# OpenMVX.net
KiCad netlist of a schematic drawn in Altium Designer
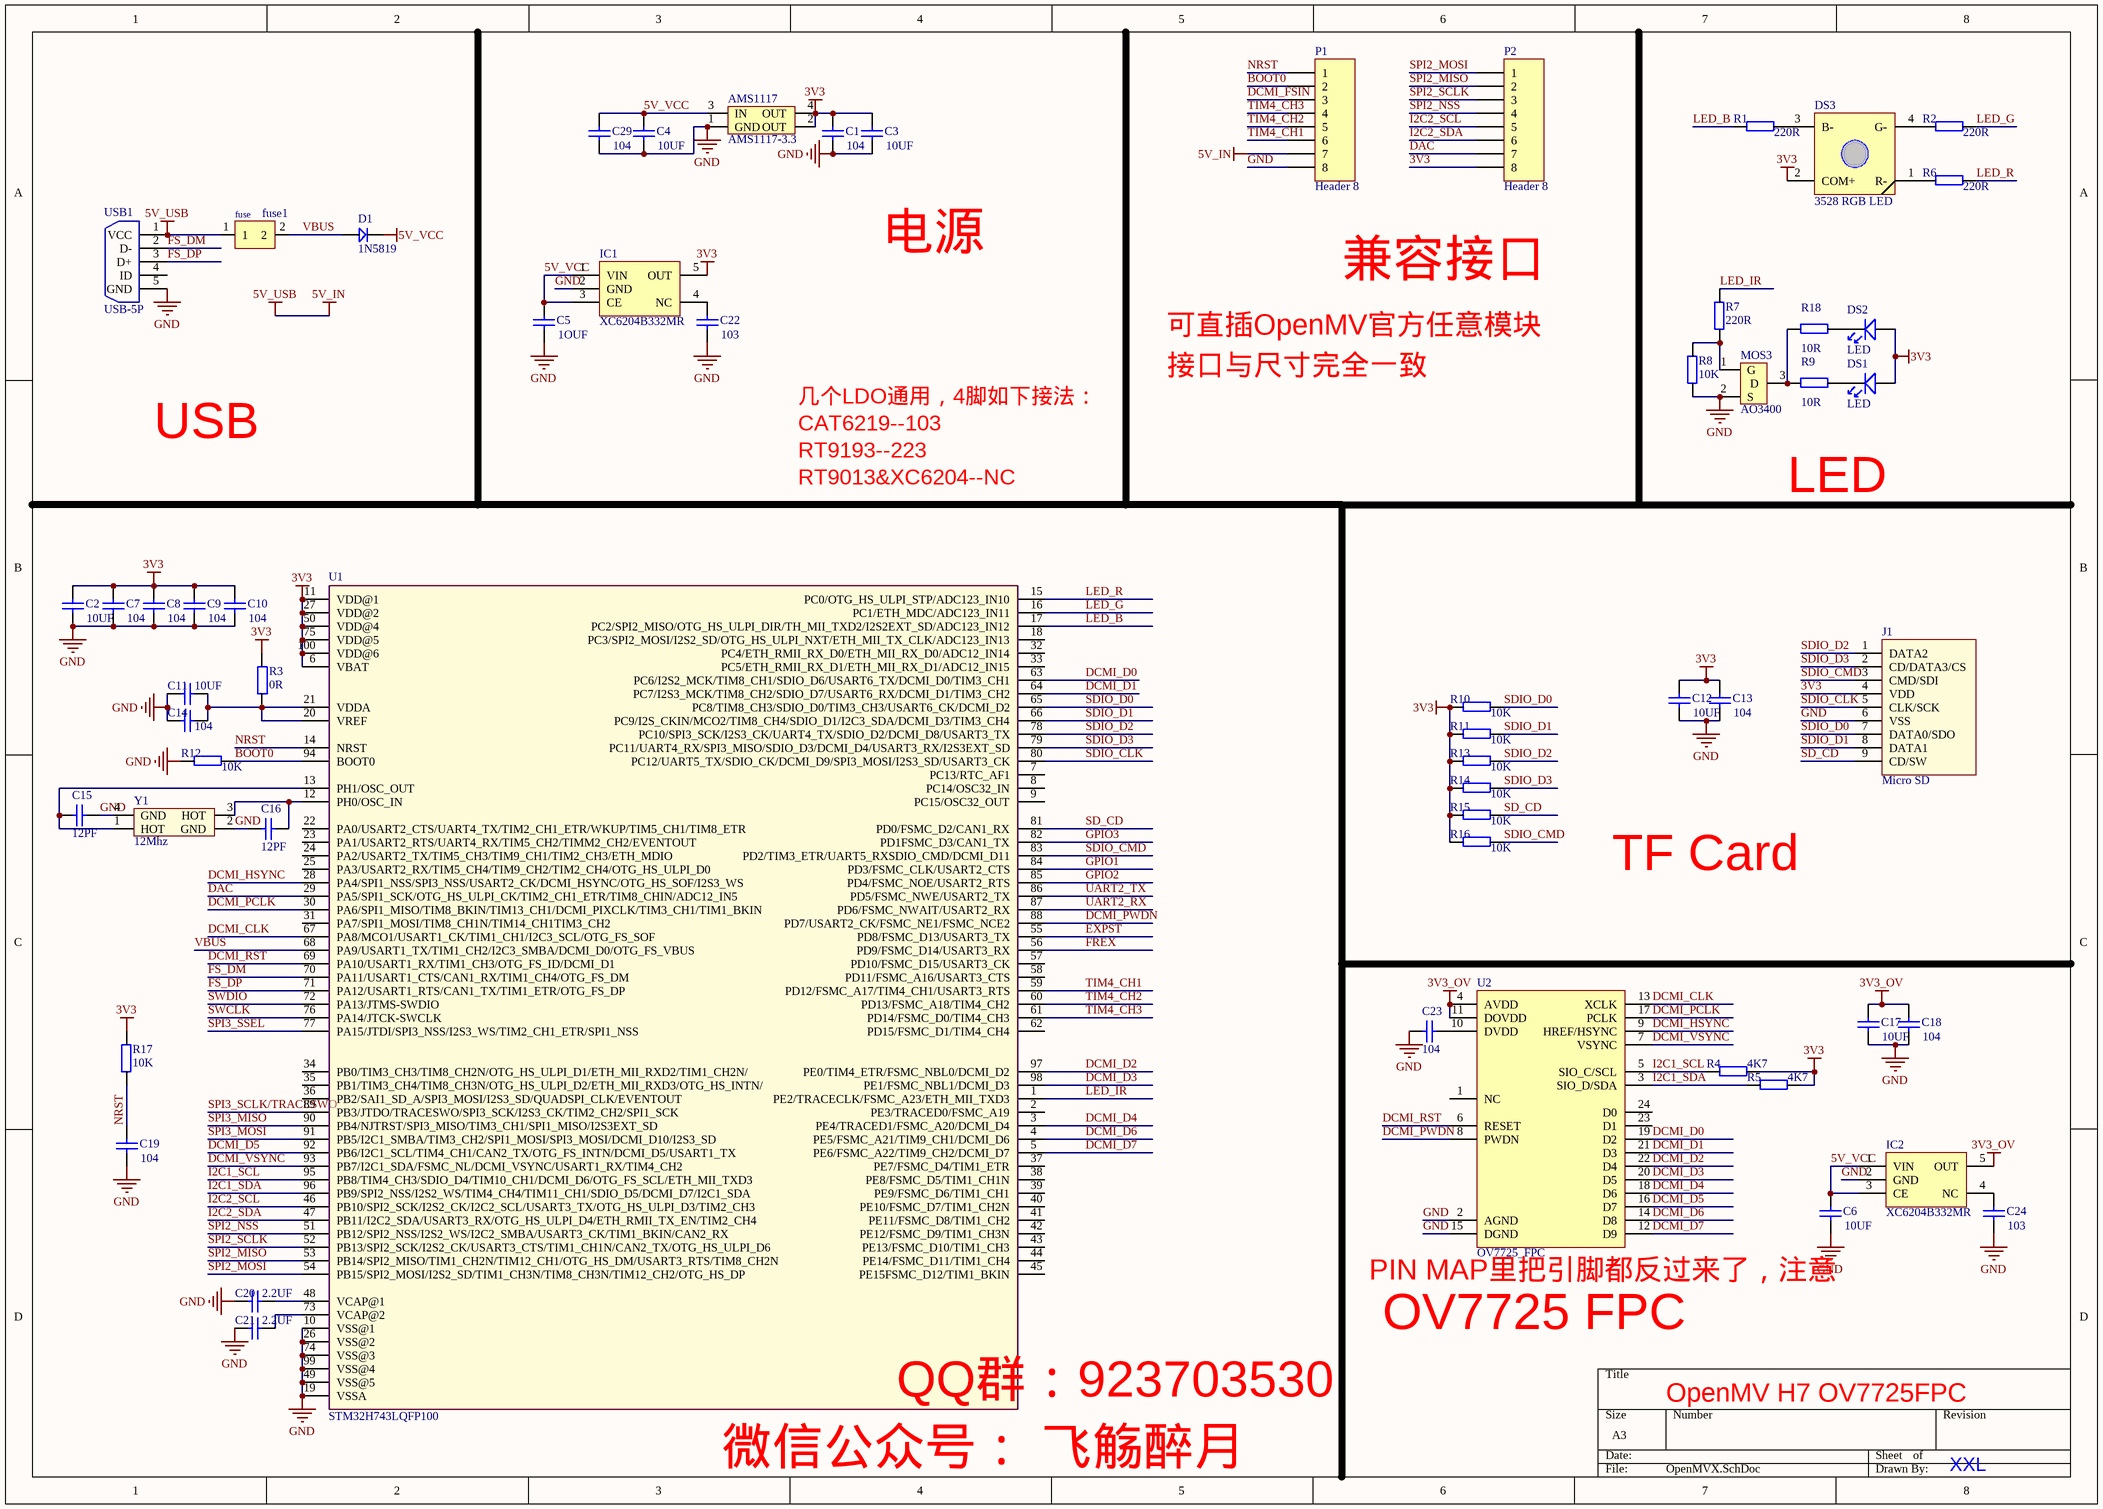
[diagram p0: OpenMVX.SchDoc]

(export (version "E")
  (design (tool "Eeschema 10.0.6"))
  (components
    (comp (ref "AMS1117")
      (value "AMS1117-3.3")
      (footprint "AMS1117")
      (libsource (lib "战舰STM32开发板底板封装库") (part "AMS1117"))
    )
    (comp (ref "C1") (value "104") (footprint "C_0603") (libsource (lib "myschlib") (part "C_0603")))
    (comp (ref "C2") (value "10UF") (footprint "C_0603") (libsource (lib "myschlib") (part "C_0603")))
    (comp (ref "C3") (value "10UF") (footprint "C_0603") (libsource (lib "myschlib") (part "C_0603")))
    (comp (ref "C4") (value "10UF") (footprint "C_0603") (libsource (lib "myschlib") (part "C_0603")))
    (comp (ref "C5") (value "1OUF") (footprint "C_0603") (libsource (lib "myschlib") (part "C_0603")))
    (comp (ref "C6") (value "10UF") (footprint "C_0603") (libsource (lib "myschlib") (part "C_0603")))
    (comp (ref "C7") (value "104") (footprint "C_0603") (libsource (lib "myschlib") (part "C_0603")))
    (comp (ref "C8") (value "104") (footprint "C_0603") (libsource (lib "myschlib") (part "C_0603")))
    (comp (ref "C9") (value "104") (footprint "C_0603") (libsource (lib "myschlib") (part "C_0603")))
    (comp (ref "C10") (value "104") (footprint "C_0603") (libsource (lib "myschlib") (part "C_0603")))
    (comp (ref "C11") (value "10UF") (footprint "C_0603") (libsource (lib "myschlib") (part "C_0603")))
    (comp (ref "C12") (value "10UF") (footprint "C_0603") (libsource (lib "myschlib") (part "C_0603")))
    (comp (ref "C13") (value "104") (footprint "C_0603") (libsource (lib "myschlib") (part "C_0603")))
    (comp (ref "C14") (value "104") (footprint "C_0603") (libsource (lib "myschlib") (part "C_0603")))
    (comp (ref "C15") (value "12PF") (footprint "C_0603") (libsource (lib "myschlib") (part "C_0603")))
    (comp (ref "C16") (value "12PF") (footprint "C_0603") (libsource (lib "myschlib") (part "C_0603")))
    (comp (ref "C17") (value "10UF") (footprint "C_0603") (libsource (lib "myschlib") (part "C_0603")))
    (comp (ref "C18") (value "104") (footprint "C_0603") (libsource (lib "myschlib") (part "C_0603")))
    (comp (ref "C19") (value "104") (footprint "C_0603") (libsource (lib "myschlib") (part "C_0603")))
    (comp (ref "C20") (value "2.2UF") (footprint "C_0603") (libsource (lib "myschlib") (part "C_0603")))
    (comp (ref "C21") (value "2.2UF") (footprint "C_0603") (libsource (lib "myschlib") (part "C_0603")))
    (comp (ref "C22") (value "103") (footprint "C_0603") (libsource (lib "myschlib") (part "C_0603")))
    (comp (ref "C23") (value "104") (footprint "C_0603") (libsource (lib "myschlib") (part "C_0603")))
    (comp (ref "C24") (value "103") (footprint "C_0603") (libsource (lib "myschlib") (part "C_0603")))
    (comp (ref "C29") (value "104") (footprint "C_0603") (libsource (lib "myschlib") (part "C_0603")))
    (comp (ref "D1")
      (value "1N5819")
      (footprint "mypcblib:SOD-323")
      (libsource (lib "战舰STM32开发板底板封装库") (part "D"))
    )
    (comp (ref "DS1") (value "LED") (footprint "mypcblib:LED-1206") (libsource (lib "myschlib") (part "LED")))
    (comp (ref "DS2") (value "LED") (footprint "mypcblib:LED-1206") (libsource (lib "myschlib") (part "LED")))
    (comp (ref "DS3")
      (value "3528 RGB LED")
      (footprint "3528/1210RGB LED")
      (libsource (lib "myschlib") (part "3528RGB LED"))
    )
    (comp (ref "fuse1") (value "fuse0603") (footprint "0603P") (libsource (lib "myschlib") (part "FUSE")))
    (comp (ref "IC1")
      (value "XC6204B332MR")
      (footprint "SOT23-5L")
      (description "LDO")
      (fields (field (name "版权归属") "源创客"))
      (libsource (lib "myschlib") (part "LDO XC6204"))
    )
    (comp (ref "IC2")
      (value "XC6204B332MR")
      (footprint "SOT23-5L")
      (description "LDO")
      (fields (field (name "版权归属") "源创客"))
      (libsource (lib "myschlib") (part "LDO XC6204"))
    )
    (comp (ref "J1")
      (value "Micro SD")
      (footprint "Micro SD")
      (description "Micro SD卡")
      (fields (field (name "版权归属") "源创客"))
      (libsource (lib "myschlib") (part "Micro SD"))
    )
    (comp (ref "MOS3")
      (value "AO3400")
      (footprint "SOT-23")
      (description "AO3400A")
      (libsource (lib "myschlib") (part "MOS-N"))
    )
    (comp (ref "P1")
      (value "Header 8")
      (footprint "1X08")
      (description "Header, 8-Pin")
      (fields (field (name "PUBLISHER") "Altium Limited"))
      (libsource (lib "myschlib") (part "Header 8"))
    )
    (comp (ref "P2")
      (value "Header 8")
      (footprint "1X08")
      (description "Header, 8-Pin")
      (fields (field (name "PUBLISHER") "Altium Limited"))
      (libsource (lib "myschlib") (part "Header 8"))
    )
    (comp (ref "R1") (value "220R") (footprint "0603P") (libsource (lib "myschlib") (part "R")))
    (comp (ref "R2") (value "220R") (footprint "0603P") (libsource (lib "myschlib") (part "R")))
    (comp (ref "R3") (value "0R") (footprint "0603P") (libsource (lib "myschlib") (part "R")))
    (comp (ref "R4") (value "4K7") (footprint "0603P") (libsource (lib "myschlib") (part "R")))
    (comp (ref "R5") (value "4K7") (footprint "0603P") (libsource (lib "myschlib") (part "R")))
    (comp (ref "R6") (value "220R") (footprint "0603P") (libsource (lib "myschlib") (part "R")))
    (comp (ref "R7") (value "220R") (footprint "0603P") (libsource (lib "myschlib") (part "R")))
    (comp (ref "R8") (value "10K") (footprint "0603P") (libsource (lib "myschlib") (part "R")))
    (comp (ref "R9") (value "10R") (footprint "0603P") (libsource (lib "myschlib") (part "R")))
    (comp (ref "R10") (value "10K") (footprint "0603P") (libsource (lib "myschlib") (part "R")))
    (comp (ref "R11") (value "10K") (footprint "0603P") (libsource (lib "myschlib") (part "R")))
    (comp (ref "R12") (value "10K") (footprint "0603P") (libsource (lib "myschlib") (part "R")))
    (comp (ref "R13") (value "10K") (footprint "0603P") (libsource (lib "myschlib") (part "R")))
    (comp (ref "R14") (value "10K") (footprint "0603P") (libsource (lib "myschlib") (part "R")))
    (comp (ref "R15") (value "10K") (footprint "0603P") (libsource (lib "myschlib") (part "R")))
    (comp (ref "R16") (value "10K") (footprint "0603P") (libsource (lib "myschlib") (part "R")))
    (comp (ref "R17") (value "10K") (footprint "0603P") (libsource (lib "myschlib") (part "R")))
    (comp (ref "R18") (value "10R") (footprint "0603P") (libsource (lib "myschlib") (part "R")))
    (comp (ref "U1")
      (value "STM32H743LQFP100")
      (footprint "LQFP-100PIN")
      (libsource (lib "myschlib") (part "STM32H743LQFP100"))
    )
    (comp (ref "U2")
      (value "OV7725_FPC")
      (footprint "FPC0.5 2H-WS-24P")
      (libsource (lib "myschlib") (part "OV7725 FPC 24P 0.5MM"))
    )
    (comp (ref "USB1")
      (value "USB-5P")
      (footprint "MICRO_USB")
      (description "微型USB母座")
      (fields (field (name "版权归属") "源创客"))
      (libsource (lib "myschlib") (part "USB-5P"))
    )
    (comp (ref "Y1")
      (value "12Mhz")
      (footprint "XTAL3225")
      (description "3225贴片无源晶振")
      (libsource (lib "STM32F767核心板封装库") (part "XTAL_3225"))
    )
  )
  (nets
    (net (code "1") (name "/BOOT0") (class "Default")
      (node (ref "P1") (pin "2") (pinfunction "2_2") (pintype "passive"))
      (node (ref "R12") (pin "1") (pintype "passive"))
      (node (ref "U1") (pin "94") (pinfunction "BOOT0_94") (pintype "passive"))
    )
    (net (code "2") (name "/DAC") (class "Default")
      (node (ref "P2") (pin "7") (pinfunction "7_7") (pintype "passive"))
      (node (ref "U1") (pin "29") (pinfunction "PA5/SPI1_SCK/OTG_HS_ULPI_CK/TIM2_CH1_ETR/TIM8_CHIN/ADC12_IN5_29") (pintype "passive"))
    )
    (net (code "3") (name "/DCMI_CLK") (class "Default")
      (node (ref "U1") (pin "67") (pinfunction "PA8/MCO1/USART1_CK/TIM1_CH1/I2C3_SCL/OTG_FS_SOF_67") (pintype "passive"))
      (node (ref "U2") (pin "13") (pinfunction "XCLK_13") (pintype "passive"))
    )
    (net (code "4") (name "/DCMI_D0") (class "Default")
      (node (ref "U1") (pin "63") (pinfunction "PC6/I2S2_MCK/TIM8_CH1/SDIO_D6/USART6_TX/DCMI_D0/TIM3_CH1_63") (pintype "passive"))
      (node (ref "U2") (pin "19") (pinfunction "D2_19") (pintype "passive"))
    )
    (net (code "5") (name "/DCMI_D1") (class "Default")
      (node (ref "U1") (pin "64") (pinfunction "PC7/I2S3_MCK/TIM8_CH2/SDIO_D7/USART6_RX/DCMI_D1/TIM3_CH2_64") (pintype "passive"))
      (node (ref "U2") (pin "21") (pinfunction "D3_21") (pintype "passive"))
    )
    (net (code "6") (name "/DCMI_D2") (class "Default")
      (node (ref "U1") (pin "97") (pinfunction "PE0/TIM4_ETR/FSMC_NBL0/DCMI_D2_97") (pintype "passive"))
      (node (ref "U2") (pin "22") (pinfunction "D4_22") (pintype "passive"))
    )
    (net (code "7") (name "/DCMI_D3") (class "Default")
      (node (ref "U1") (pin "98") (pinfunction "PE1/FSMC_NBL1/DCMI_D3_98") (pintype "passive"))
      (node (ref "U2") (pin "20") (pinfunction "D5_20") (pintype "passive"))
    )
    (net (code "8") (name "/DCMI_D4") (class "Default")
      (node (ref "U1") (pin "3") (pinfunction "PE4/TRACED1/FSMC_A20/DCMI_D4_3") (pintype "passive"))
      (node (ref "U2") (pin "18") (pinfunction "D6_18") (pintype "passive"))
    )
    (net (code "9") (name "/DCMI_D5") (class "Default")
      (node (ref "U1") (pin "92") (pinfunction "PB6/I2C1_SCL/TIM4_CH1/CAN2_TX/OTG_FS_INTN/DCMI_D5/USART1_TX_92") (pintype "passive"))
      (node (ref "U2") (pin "16") (pinfunction "D7_16") (pintype "passive"))
    )
    (net (code "10") (name "/DCMI_D6") (class "Default")
      (node (ref "U1") (pin "4") (pinfunction "PE5/FSMC_A21/TIM9_CH1/DCMI_D6_4") (pintype "passive"))
      (node (ref "U2") (pin "14") (pinfunction "D8_14") (pintype "passive"))
    )
    (net (code "11") (name "/DCMI_D7") (class "Default")
      (node (ref "U1") (pin "5") (pinfunction "PE6/FSMC_A22/TIM9_CH2/DCMI_D7_5") (pintype "passive"))
      (node (ref "U2") (pin "12") (pinfunction "D9_12") (pintype "passive"))
    )
    (net (code "12") (name "/DCMI_FSIN") (class "Default")
      (node (ref "P1") (pin "3") (pinfunction "3_3") (pintype "passive"))
    )
    (net (code "13") (name "/DCMI_HSYNC") (class "Default")
      (node (ref "U1") (pin "28") (pinfunction "PA4/SPI1_NSS/SPI3_NSS/USART2_CK/DCMI_HSYNC/OTG_HS_SOF/I2S3_WS_28") (pintype "passive"))
      (node (ref "U2") (pin "9") (pinfunction "HREF/HSYNC_9") (pintype "passive"))
    )
    (net (code "14") (name "/DCMI_PCLK") (class "Default")
      (node (ref "U1") (pin "30") (pinfunction "PA6/SPI1_MISO/TIM8_BKIN/TIM13_CH1/DCMI_PIXCLK/TIM3_CH1/TIM1_BKIN_30") (pintype "passive"))
      (node (ref "U2") (pin "17") (pinfunction "PCLK_17") (pintype "passive"))
    )
    (net (code "15") (name "/DCMI_PWDN") (class "Default")
      (node (ref "U1") (pin "88") (pinfunction "PD7/USART2_CK/FSMC_NE1/FSMC_NCE2_88") (pintype "passive"))
      (node (ref "U2") (pin "8") (pinfunction "PWDN_8") (pintype "passive"))
    )
    (net (code "16") (name "/DCMI_RST") (class "Default")
      (node (ref "U1") (pin "69") (pinfunction "PA10/USART1_RX/TIM1_CH3/OTG_FS_ID/DCMI_D1_69") (pintype "passive"))
      (node (ref "U2") (pin "6") (pinfunction "RESET_6") (pintype "passive"))
    )
    (net (code "17") (name "/DCMI_VSYNC") (class "Default")
      (node (ref "U1") (pin "93") (pinfunction "PB7/I2C1_SDA/FSMC_NL/DCMI_VSYNC/USART1_RX/TIM4_CH2_93") (pintype "passive"))
      (node (ref "U2") (pin "7") (pinfunction "VSYNC_7") (pintype "passive"))
    )
    (net (code "18") (name "/EXPST") (class "Default")
      (node (ref "U1") (pin "55") (pinfunction "PD8/FSMC_D13/USART3_TX_55") (pintype "passive"))
    )
    (net (code "19") (name "/FREX") (class "Default")
      (node (ref "U1") (pin "56") (pinfunction "PD9/FSMC_D14/USART3_RX_56") (pintype "passive"))
    )
    (net (code "20") (name "/FS_DM") (class "Default")
      (node (ref "U1") (pin "70") (pinfunction "PA11/USART1_CTS/CAN1_RX/TIM1_CH4/OTG_FS_DM_70") (pintype "passive"))
      (node (ref "USB1") (pin "2") (pinfunction "D-_2") (pintype "passive"))
    )
    (net (code "21") (name "/FS_DP") (class "Default")
      (node (ref "U1") (pin "71") (pinfunction "PA12/USART1_RTS/CAN1_TX/TIM1_ETR/OTG_FS_DP_71") (pintype "passive"))
      (node (ref "USB1") (pin "3") (pinfunction "D+_3") (pintype "passive"))
    )
    (net (code "22") (name "/GPIO1") (class "Default")
      (node (ref "U1") (pin "84") (pinfunction "PD3/FSMC_CLK/USART2_CTS_84") (pintype "passive"))
    )
    (net (code "23") (name "/GPIO2") (class "Default")
      (node (ref "U1") (pin "85") (pinfunction "PD4/FSMC_NOE/USART2_RTS_85") (pintype "passive"))
    )
    (net (code "24") (name "/GPIO3") (class "Default")
      (node (ref "U1") (pin "82") (pinfunction "PD1FSMC_D3/CAN1_TX_82") (pintype "passive"))
    )
    (net (code "25") (name "/I2C1_SCL") (class "Default")
      (node (ref "R4") (pin "2") (pintype "passive"))
      (node (ref "U1") (pin "95") (pinfunction "PB8/TIM4_CH3/SDIO_D4/TIM10_CH1/DCMI_D6/OTG_FS_SCL/ETH_MII_TXD3_95") (pintype "passive"))
      (node (ref "U2") (pin "5") (pinfunction "SIO_C/SCL_5") (pintype "passive"))
    )
    (net (code "26") (name "/I2C1_SDA") (class "Default")
      (node (ref "R5") (pin "2") (pintype "passive"))
      (node (ref "U1") (pin "96") (pinfunction "PB9/SPI2_NSS/I2S2_WS/TIM4_CH4/TIM11_CH1/SDIO_D5/DCMI_D7/I2C1_SDA_96") (pintype "passive"))
      (node (ref "U2") (pin "3") (pinfunction "SIO_D/SDA_3") (pintype "passive"))
    )
    (net (code "27") (name "/I2C2_SCL") (class "Default")
      (node (ref "P2") (pin "5") (pinfunction "5_5") (pintype "passive"))
      (node (ref "U1") (pin "46") (pinfunction "PB10/SPI2_SCK/I2S2_CK/I2C2_SCL/USART3_TX/OTG_HS_ULPI_D3/TIM2_CH3_46") (pintype "passive"))
    )
    (net (code "28") (name "/I2C2_SDA") (class "Default")
      (node (ref "P2") (pin "6") (pinfunction "6_6") (pintype "passive"))
      (node (ref "U1") (pin "47") (pinfunction "PB11/I2C2_SDA/USART3_RX/OTG_HS_ULPI_D4/ETH_RMII_TX_EN/TIM2_CH4_47") (pintype "passive"))
    )
    (net (code "29") (name "/LED_B") (class "Default")
      (node (ref "R1") (pin "2") (pintype "passive"))
      (node (ref "U1") (pin "17") (pinfunction "PC2/SPI2_MISO/OTG_HS_ULPI_DIR/TH_MII_TXD2/I2S2EXT_SD/ADC123_IN12_17") (pintype "passive"))
    )
    (net (code "30") (name "/LED_G") (class "Default")
      (node (ref "R2") (pin "1") (pintype "passive"))
      (node (ref "U1") (pin "16") (pinfunction "PC1/ETH_MDC/ADC123_IN11_16") (pintype "passive"))
    )
    (net (code "31") (name "/LED_IR") (class "Default")
      (node (ref "R7") (pin "1") (pintype "passive"))
      (node (ref "U1") (pin "1") (pinfunction "PE2/TRACECLK/FSMC_A23/ETH_MII_TXD3_1") (pintype "passive"))
    )
    (net (code "32") (name "/LED_R") (class "Default")
      (node (ref "R6") (pin "1") (pintype "passive"))
      (node (ref "U1") (pin "15") (pinfunction "PC0/OTG_HS_ULPI_STP/ADC123_IN10_15") (pintype "passive"))
    )
    (net (code "33") (name "/NRST") (class "Default")
      (node (ref "C19") (pin "2") (pinfunction "2_2") (pintype "passive"))
      (node (ref "P1") (pin "1") (pinfunction "1_1") (pintype "passive"))
      (node (ref "R17") (pin "2") (pintype "passive"))
      (node (ref "U1") (pin "14") (pinfunction "NRST_14") (pintype "passive"))
    )
    (net (code "34") (name "/SDIO_CLK") (class "Default")
      (node (ref "J1") (pin "5") (pinfunction "CLK/SCK_5") (pintype "passive"))
      (node (ref "U1") (pin "80") (pinfunction "PC12/UART5_TX/SDIO_CK/DCMI_D9/SPI3_MOSI/I2S3_SD/USART3_CK_80") (pintype "passive"))
    )
    (net (code "35") (name "/SDIO_CMD") (class "Default")
      (node (ref "J1") (pin "3") (pinfunction "CMD/SDI_3") (pintype "passive"))
      (node (ref "R16") (pin "1") (pintype "passive"))
      (node (ref "U1") (pin "83") (pinfunction "PD2/TIM3_ETR/UART5_RXSDIO_CMD/DCMI_D11_83") (pintype "passive"))
    )
    (net (code "36") (name "/SDIO_D0") (class "Default")
      (node (ref "J1") (pin "7") (pinfunction "DATA0/SDO_7") (pintype "passive"))
      (node (ref "R10") (pin "1") (pintype "passive"))
      (node (ref "U1") (pin "65") (pinfunction "PC8/TIM8_CH3/SDIO_D0/TIM3_CH3/USART6_CK/DCMI_D2_65") (pintype "passive"))
    )
    (net (code "37") (name "/SDIO_D1") (class "Default")
      (node (ref "J1") (pin "8") (pinfunction "DATA1_8") (pintype "passive"))
      (node (ref "R11") (pin "1") (pintype "passive"))
      (node (ref "U1") (pin "66") (pinfunction "PC9/I2S_CKIN/MCO2/TIM8_CH4/SDIO_D1/I2C3_SDA/DCMI_D3/TIM3_CH4_66") (pintype "passive"))
    )
    (net (code "38") (name "/SDIO_D2") (class "Default")
      (node (ref "J1") (pin "1") (pinfunction "DATA2_1") (pintype "passive"))
      (node (ref "R13") (pin "1") (pintype "passive"))
      (node (ref "U1") (pin "78") (pinfunction "PC10/SPI3_SCK/I2S3_CK/UART4_TX/SDIO_D2/DCMI_D8/USART3_TX_78") (pintype "passive"))
    )
    (net (code "39") (name "/SDIO_D3") (class "Default")
      (node (ref "J1") (pin "2") (pinfunction "CD/DATA3/CS_2") (pintype "passive"))
      (node (ref "R14") (pin "1") (pintype "passive"))
      (node (ref "U1") (pin "79") (pinfunction "PC11/UART4_RX/SPI3_MISO/SDIO_D3/DCMI_D4/USART3_RX/I2S3EXT_SD_79") (pintype "passive"))
    )
    (net (code "40") (name "/SD_CD") (class "Default")
      (node (ref "J1") (pin "9") (pinfunction "CD/SW_9") (pintype "passive"))
      (node (ref "R15") (pin "1") (pintype "passive"))
      (node (ref "U1") (pin "81") (pinfunction "PD0/FSMC_D2/CAN1_RX_81") (pintype "passive"))
    )
    (net (code "41") (name "/SPI2_MISO") (class "Default")
      (node (ref "P2") (pin "2") (pinfunction "2_2") (pintype "passive"))
      (node (ref "U1") (pin "53") (pinfunction "PB14/SPI2_MISO/TIM1_CH2N/TIM12_CH1/OTG_HS_DM/USART3_RTS/TIM8_CH2N_53") (pintype "passive"))
    )
    (net (code "42") (name "/SPI2_MOSI") (class "Default")
      (node (ref "P2") (pin "1") (pinfunction "1_1") (pintype "passive"))
      (node (ref "U1") (pin "54") (pinfunction "PB15/SPI2_MOSI/I2S2_SD/TIM1_CH3N/TIM8_CH3N/TIM12_CH2/OTG_HS_DP_54") (pintype "passive"))
    )
    (net (code "43") (name "/SPI2_NSS") (class "Default")
      (node (ref "P2") (pin "4") (pinfunction "4_4") (pintype "passive"))
      (node (ref "U1") (pin "51") (pinfunction "PB12/SPI2_NSS/I2S2_WS/I2C2_SMBA/USART3_CK/TIM1_BKIN/CAN2_RX_51") (pintype "passive"))
    )
    (net (code "44") (name "/SPI2_SCLK") (class "Default")
      (node (ref "P2") (pin "3") (pinfunction "3_3") (pintype "passive"))
      (node (ref "U1") (pin "52") (pinfunction "PB13/SPI2_SCK/I2S2_CK/USART3_CTS/TIM1_CH1N/CAN2_TX/OTG_HS_ULPI_D6_52") (pintype "passive"))
    )
    (net (code "45") (name "/SPI3_MISO") (class "Default")
      (node (ref "U1") (pin "90") (pinfunction "PB4/NJTRST/SPI3_MISO/TIM3_CH1/SPI1_MISO/I2S3EXT_SD_90") (pintype "passive"))
    )
    (net (code "46") (name "/SPI3_MOSI") (class "Default")
      (node (ref "U1") (pin "91") (pinfunction "PB5/I2C1_SMBA/TIM3_CH2/SPI1_MOSI/SPI3_MOSI/DCMI_D10/I2S3_SD_91") (pintype "passive"))
    )
    (net (code "47") (name "/SPI3_SCLK{slash}TRACESWO") (class "Default")
      (node (ref "U1") (pin "89") (pinfunction "PB3/JTDO/TRACESWO/SPI3_SCK/I2S3_CK/TIM2_CH2/SPI1_SCK_89") (pintype "passive"))
    )
    (net (code "48") (name "/SPI3_SSEL") (class "Default")
      (node (ref "U1") (pin "77") (pinfunction "PA15/JTDI/SPI3_NSS/I2S3_WS/TIM2_CH1_ETR/SPI1_NSS_77") (pintype "passive"))
    )
    (net (code "49") (name "/SWCLK") (class "Default")
      (node (ref "U1") (pin "76") (pinfunction "PA14/JTCK-SWCLK_76") (pintype "passive"))
    )
    (net (code "50") (name "/SWDIO") (class "Default")
      (node (ref "U1") (pin "72") (pinfunction "PA13/JTMS-SWDIO_72") (pintype "passive"))
    )
    (net (code "51") (name "/TIM4_CH1") (class "Default")
      (node (ref "P1") (pin "6") (pinfunction "6_6") (pintype "passive"))
      (node (ref "U1") (pin "59") (pinfunction "PD12/FSMC_A17/TIM4_CH1/USART3_RTS_59") (pintype "passive"))
    )
    (net (code "52") (name "/TIM4_CH2") (class "Default")
      (node (ref "P1") (pin "5") (pinfunction "5_5") (pintype "passive"))
      (node (ref "U1") (pin "60") (pinfunction "PD13/FSMC_A18/TIM4_CH2_60") (pintype "passive"))
    )
    (net (code "53") (name "/TIM4_CH3") (class "Default")
      (node (ref "P1") (pin "4") (pinfunction "4_4") (pintype "passive"))
      (node (ref "U1") (pin "61") (pinfunction "PD14/FSMC_D0/TIM4_CH3_61") (pintype "passive"))
    )
    (net (code "54") (name "/UART2_RX") (class "Default")
      (node (ref "U1") (pin "87") (pinfunction "PD6/FSMC_NWAIT/USART2_RX_87") (pintype "passive"))
    )
    (net (code "55") (name "/UART2_TX") (class "Default")
      (node (ref "U1") (pin "86") (pinfunction "PD5/FSMC_NWE/USART2_TX_86") (pintype "passive"))
    )
    (net (code "56") (name "/VBUS") (class "Default")
      (node (ref "D1") (pin "1") (pintype "passive"))
      (node (ref "U1") (pin "68") (pinfunction "PA9/USART1_TX/TIM1_CH2/I2C3_SMBA/DCMI_D0/OTG_FS_VBUS_68") (pintype "passive"))
      (node (ref "fuse1") (pin "2") (pinfunction "2_2") (pintype "passive"))
    )
    (net (code "57") (name "3V3") (class "Default")
      (node (ref "AMS1117") (pin "2") (pinfunction "OUT_2") (pintype "passive"))
      (node (ref "AMS1117") (pin "4") (pinfunction "OUT_4") (pintype "passive"))
      (node (ref "C1") (pin "2") (pinfunction "2_2") (pintype "passive"))
      (node (ref "C10") (pin "2") (pinfunction "2_2") (pintype "passive"))
      (node (ref "C12") (pin "2") (pinfunction "2_2") (pintype "passive"))
      (node (ref "C13") (pin "2") (pinfunction "2_2") (pintype "passive"))
      (node (ref "C2") (pin "2") (pinfunction "2_2") (pintype "passive"))
      (node (ref "C3") (pin "2") (pinfunction "2_2") (pintype "passive"))
      (node (ref "C7") (pin "2") (pinfunction "2_2") (pintype "passive"))
      (node (ref "C8") (pin "2") (pinfunction "2_2") (pintype "passive"))
      (node (ref "C9") (pin "2") (pinfunction "2_2") (pintype "passive"))
      (node (ref "DS1") (pin "1") (pinfunction "1_1") (pintype "passive"))
      (node (ref "DS2") (pin "1") (pinfunction "1_1") (pintype "passive"))
      (node (ref "DS3") (pin "2") (pinfunction "COM+_2") (pintype "passive"))
      (node (ref "IC1") (pin "5") (pinfunction "OUT_5") (pintype "passive"))
      (node (ref "J1") (pin "4") (pinfunction "VDD_4") (pintype "passive"))
      (node (ref "P2") (pin "8") (pinfunction "8_8") (pintype "passive"))
      (node (ref "R10") (pin "2") (pintype "passive"))
      (node (ref "R11") (pin "2") (pintype "passive"))
      (node (ref "R13") (pin "2") (pintype "passive"))
      (node (ref "R14") (pin "2") (pintype "passive"))
      (node (ref "R15") (pin "2") (pintype "passive"))
      (node (ref "R16") (pin "2") (pintype "passive"))
      (node (ref "R17") (pin "1") (pintype "passive"))
      (node (ref "R3") (pin "2") (pintype "passive"))
      (node (ref "R4") (pin "1") (pintype "passive"))
      (node (ref "R5") (pin "1") (pintype "passive"))
      (node (ref "U1") (pin "100") (pinfunction "VDD@6_100") (pintype "passive"))
      (node (ref "U1") (pin "11") (pinfunction "VDD@1_11") (pintype "passive"))
      (node (ref "U1") (pin "27") (pinfunction "VDD@2_27") (pintype "passive"))
      (node (ref "U1") (pin "50") (pinfunction "VDD@4_50") (pintype "passive"))
      (node (ref "U1") (pin "6") (pinfunction "VBAT_6") (pintype "passive"))
      (node (ref "U1") (pin "75") (pinfunction "VDD@5_75") (pintype "passive"))
    )
    (net (code "58") (name "3V3_OV") (class "Default")
      (node (ref "C17") (pin "2") (pinfunction "2_2") (pintype "passive"))
      (node (ref "C18") (pin "2") (pinfunction "2_2") (pintype "passive"))
      (node (ref "IC2") (pin "5") (pinfunction "OUT_5") (pintype "passive"))
      (node (ref "U2") (pin "11") (pinfunction "DOVDD_11") (pintype "passive"))
      (node (ref "U2") (pin "4") (pinfunction "AVDD_4") (pintype "passive"))
    )
    (net (code "59") (name "5V_IN") (class "Default")
      (node (ref "P1") (pin "7") (pinfunction "7_7") (pintype "passive"))
      (node (ref "USB1") (pin "1") (pinfunction "VCC_1") (pintype "passive"))
      (node (ref "fuse1") (pin "1") (pinfunction "1_1") (pintype "passive"))
    )
    (net (code "60") (name "5V_VCC") (class "Default")
      (node (ref "AMS1117") (pin "3") (pinfunction "IN_3") (pintype "passive"))
      (node (ref "C29") (pin "2") (pinfunction "2_2") (pintype "passive"))
      (node (ref "C4") (pin "2") (pinfunction "2_2") (pintype "passive"))
      (node (ref "C5") (pin "2") (pinfunction "2_2") (pintype "passive"))
      (node (ref "C6") (pin "2") (pinfunction "2_2") (pintype "passive"))
      (node (ref "D1") (pin "2") (pintype "passive"))
      (node (ref "IC1") (pin "1") (pinfunction "VIN_1") (pintype "passive"))
      (node (ref "IC1") (pin "3") (pinfunction "CE_3") (pintype "passive"))
      (node (ref "IC2") (pin "1") (pinfunction "VIN_1") (pintype "passive"))
      (node (ref "IC2") (pin "3") (pinfunction "CE_3") (pintype "passive"))
    )
    (net (code "61") (name "GND") (class "Default")
      (node (ref "AMS1117") (pin "1") (pinfunction "GND_1") (pintype "passive"))
      (node (ref "C1") (pin "1") (pinfunction "1_1") (pintype "passive"))
      (node (ref "C10") (pin "1") (pinfunction "1_1") (pintype "passive"))
      (node (ref "C11") (pin "2") (pinfunction "2_2") (pintype "passive"))
      (node (ref "C12") (pin "1") (pinfunction "1_1") (pintype "passive"))
      (node (ref "C13") (pin "1") (pinfunction "1_1") (pintype "passive"))
      (node (ref "C14") (pin "2") (pinfunction "2_2") (pintype "passive"))
      (node (ref "C15") (pin "1") (pinfunction "1_1") (pintype "passive"))
      (node (ref "C16") (pin "2") (pinfunction "2_2") (pintype "passive"))
      (node (ref "C17") (pin "1") (pinfunction "1_1") (pintype "passive"))
      (node (ref "C18") (pin "1") (pinfunction "1_1") (pintype "passive"))
      (node (ref "C19") (pin "1") (pinfunction "1_1") (pintype "passive"))
      (node (ref "C2") (pin "1") (pinfunction "1_1") (pintype "passive"))
      (node (ref "C20") (pin "2") (pinfunction "2_2") (pintype "passive"))
      (node (ref "C21") (pin "2") (pinfunction "2_2") (pintype "passive"))
      (node (ref "C22") (pin "1") (pinfunction "1_1") (pintype "passive"))
      (node (ref "C23") (pin "2") (pinfunction "2_2") (pintype "passive"))
      (node (ref "C24") (pin "1") (pinfunction "1_1") (pintype "passive"))
      (node (ref "C29") (pin "1") (pinfunction "1_1") (pintype "passive"))
      (node (ref "C3") (pin "1") (pinfunction "1_1") (pintype "passive"))
      (node (ref "C4") (pin "1") (pinfunction "1_1") (pintype "passive"))
      (node (ref "C5") (pin "1") (pinfunction "1_1") (pintype "passive"))
      (node (ref "C6") (pin "1") (pinfunction "1_1") (pintype "passive"))
      (node (ref "C7") (pin "1") (pinfunction "1_1") (pintype "passive"))
      (node (ref "C8") (pin "1") (pinfunction "1_1") (pintype "passive"))
      (node (ref "C9") (pin "1") (pinfunction "1_1") (pintype "passive"))
      (node (ref "IC1") (pin "2") (pinfunction "GND_2") (pintype "passive"))
      (node (ref "IC2") (pin "2") (pinfunction "GND_2") (pintype "passive"))
      (node (ref "J1") (pin "6") (pinfunction "VSS_6") (pintype "passive"))
      (node (ref "MOS3") (pin "2") (pinfunction "S_2") (pintype "passive"))
      (node (ref "P1") (pin "8") (pinfunction "8_8") (pintype "passive"))
      (node (ref "R12") (pin "2") (pintype "passive"))
      (node (ref "R8") (pin "2") (pintype "passive"))
      (node (ref "U1") (pin "10") (pinfunction "VSS@1_10") (pintype "passive"))
      (node (ref "U1") (pin "19") (pinfunction "VSSA_19") (pintype "passive"))
      (node (ref "U1") (pin "26") (pinfunction "VSS@2_26") (pintype "passive"))
      (node (ref "U1") (pin "49") (pinfunction "VSS@5_49") (pintype "passive"))
      (node (ref "U1") (pin "74") (pinfunction "VSS@3_74") (pintype "passive"))
      (node (ref "U1") (pin "99") (pinfunction "VSS@4_99") (pintype "passive"))
      (node (ref "U2") (pin "15") (pinfunction "DGND_15") (pintype "passive"))
      (node (ref "U2") (pin "2") (pinfunction "AGND_2") (pintype "passive"))
      (node (ref "USB1") (pin "5") (pinfunction "GND_5") (pintype "passive"))
      (node (ref "Y1") (pin "2") (pinfunction "GND_2") (pintype "passive"))
      (node (ref "Y1") (pin "4") (pinfunction "GND_4") (pintype "passive"))
    )
    (net (code "62") (name "Net-(DS1-Pad2)") (class "Default")
      (node (ref "DS1") (pin "2") (pinfunction "2_2") (pintype "passive"))
      (node (ref "R9") (pin "1") (pintype "passive"))
    )
    (net (code "63") (name "Net-(DS2-Pad2)") (class "Default")
      (node (ref "DS2") (pin "2") (pinfunction "2_2") (pintype "passive"))
      (node (ref "R18") (pin "1") (pintype "passive"))
    )
    (net (code "64") (name "Net-(DS3-B-)") (class "Default")
      (node (ref "DS3") (pin "3") (pinfunction "B-_3") (pintype "passive"))
      (node (ref "R1") (pin "1") (pintype "passive"))
    )
    (net (code "65") (name "Net-(DS3-G-)") (class "Default")
      (node (ref "DS3") (pin "4") (pinfunction "G-_4") (pintype "passive"))
      (node (ref "R2") (pin "2") (pintype "passive"))
    )
    (net (code "66") (name "Net-(DS3-R-)") (class "Default")
      (node (ref "DS3") (pin "1") (pinfunction "R-_1") (pintype "passive"))
      (node (ref "R6") (pin "2") (pintype "passive"))
    )
    (net (code "67") (name "Net-(IC1-NC)") (class "Default")
      (node (ref "C22") (pin "2") (pinfunction "2_2") (pintype "passive"))
      (node (ref "IC1") (pin "4") (pinfunction "NC_4") (pintype "passive"))
    )
    (net (code "68") (name "Net-(IC2-NC)") (class "Default")
      (node (ref "C24") (pin "2") (pinfunction "2_2") (pintype "passive"))
      (node (ref "IC2") (pin "4") (pinfunction "NC_4") (pintype "passive"))
    )
    (net (code "69") (name "Net-(MOS3-D)") (class "Default")
      (node (ref "MOS3") (pin "3") (pinfunction "D_3") (pintype "passive"))
      (node (ref "R18") (pin "2") (pintype "passive"))
      (node (ref "R9") (pin "2") (pintype "passive"))
    )
    (net (code "70") (name "Net-(MOS3-G)") (class "Default")
      (node (ref "MOS3") (pin "1") (pinfunction "G_1") (pintype "passive"))
      (node (ref "R7") (pin "2") (pintype "passive"))
      (node (ref "R8") (pin "1") (pintype "passive"))
    )
    (net (code "71") (name "Net-(U1-PH0{slash}OSC_IN)") (class "Default")
      (node (ref "C16") (pin "1") (pinfunction "1_1") (pintype "passive"))
      (node (ref "U1") (pin "12") (pinfunction "PH0/OSC_IN_12") (pintype "passive"))
      (node (ref "Y1") (pin "3") (pinfunction "HOT_3") (pintype "passive"))
    )
    (net (code "72") (name "Net-(U1-PH1{slash}OSC_OUT)") (class "Default")
      (node (ref "C15") (pin "2") (pinfunction "2_2") (pintype "passive"))
      (node (ref "U1") (pin "13") (pinfunction "PH1/OSC_OUT_13") (pintype "passive"))
      (node (ref "Y1") (pin "1") (pinfunction "HOT_1") (pintype "passive"))
    )
    (net (code "73") (name "Net-(U1-VCAP@1)") (class "Default")
      (node (ref "C20") (pin "1") (pinfunction "1_1") (pintype "passive"))
      (node (ref "U1") (pin "48") (pinfunction "VCAP@1_48") (pintype "passive"))
    )
    (net (code "74") (name "Net-(U1-VCAP@2)") (class "Default")
      (node (ref "C21") (pin "1") (pinfunction "1_1") (pintype "passive"))
      (node (ref "U1") (pin "73") (pinfunction "VCAP@2_73") (pintype "passive"))
    )
    (net (code "75") (name "Net-(U1-VDDA)") (class "Default")
      (node (ref "C11") (pin "1") (pinfunction "1_1") (pintype "passive"))
      (node (ref "C14") (pin "1") (pinfunction "1_1") (pintype "passive"))
      (node (ref "R3") (pin "1") (pintype "passive"))
      (node (ref "U1") (pin "20") (pinfunction "VREF_20") (pintype "passive"))
      (node (ref "U1") (pin "21") (pinfunction "VDDA_21") (pintype "passive"))
    )
    (net (code "76") (name "Net-(U2-DVDD)") (class "Default")
      (node (ref "C23") (pin "1") (pinfunction "1_1") (pintype "passive"))
      (node (ref "U2") (pin "10") (pinfunction "DVDD_10") (pintype "passive"))
    )
    (net (code "77") (name "unconnected-(U1-PA0{slash}USART2_CTS{slash}UART4_TX{slash}TIM2_CH1_ETR{slash}WKUP{slash}TIM5_CH1{slash}TIM8_ETR-Pad22)") (class "Default")
      (node (ref "U1") (pin "22") (pinfunction "PA0/USART2_CTS/UART4_TX/TIM2_CH1_ETR/WKUP/TIM5_CH1/TIM8_ETR_22") (pintype "passive"))
    )
    (net (code "78") (name "unconnected-(U1-PA1{slash}USART2_RTS{slash}UART4_RX{slash}TIM5_CH2{slash}TIMM2_CH2{slash}EVENTOUT-Pad23)") (class "Default")
      (node (ref "U1") (pin "23") (pinfunction "PA1/USART2_RTS/UART4_RX/TIM5_CH2/TIMM2_CH2/EVENTOUT_23") (pintype "passive"))
    )
    (net (code "79") (name "unconnected-(U1-PA2{slash}USART2_TX{slash}TIM5_CH3{slash}TIM9_CH1{slash}TIM2_CH3{slash}ETH_MDIO-Pad24)") (class "Default")
      (node (ref "U1") (pin "24") (pinfunction "PA2/USART2_TX/TIM5_CH3/TIM9_CH1/TIM2_CH3/ETH_MDIO_24") (pintype "passive"))
    )
    (net (code "80") (name "unconnected-(U1-PA3{slash}USART2_RX{slash}TIM5_CH4{slash}TIM9_CH2{slash}TIM2_CH4{slash}OTG_HS_ULPI_D0-Pad25)") (class "Default")
      (node (ref "U1") (pin "25") (pinfunction "PA3/USART2_RX/TIM5_CH4/TIM9_CH2/TIM2_CH4/OTG_HS_ULPI_D0_25") (pintype "passive"))
    )
    (net (code "81") (name "unconnected-(U1-PA7{slash}SPI1_MOSI{slash}TIM8_CH1N{slash}TIM14_CH1TIM3_CH2-Pad31)") (class "Default")
      (node (ref "U1") (pin "31") (pinfunction "PA7/SPI1_MOSI/TIM8_CH1N/TIM14_CH1TIM3_CH2_31") (pintype "passive"))
    )
    (net (code "82") (name "unconnected-(U1-PB0{slash}TIM3_CH3{slash}TIM8_CH2N{slash}OTG_HS_ULPI_D1{slash}ETH_MII_RXD2{slash}TIM1_CH2N{slash}-Pad34)") (class "Default")
      (node (ref "U1") (pin "34") (pinfunction "PB0/TIM3_CH3/TIM8_CH2N/OTG_HS_ULPI_D1/ETH_MII_RXD2/TIM1_CH2N/_34") (pintype "passive"))
    )
    (net (code "83") (name "unconnected-(U1-PB1{slash}TIM3_CH4{slash}TIM8_CH3N{slash}OTG_HS_ULPI_D2{slash}ETH_MII_RXD3{slash}OTG_HS_INTN{slash}-Pad35)") (class "Default")
      (node (ref "U1") (pin "35") (pinfunction "PB1/TIM3_CH4/TIM8_CH3N/OTG_HS_ULPI_D2/ETH_MII_RXD3/OTG_HS_INTN/_35") (pintype "passive"))
    )
    (net (code "84") (name "unconnected-(U1-PB2{slash}SAI1_SD_A{slash}SPI3_MOSI{slash}I2S3_SD{slash}QUADSPI_CLK{slash}EVENTOUT-Pad36)") (class "Default")
      (node (ref "U1") (pin "36") (pinfunction "PB2/SAI1_SD_A/SPI3_MOSI/I2S3_SD/QUADSPI_CLK/EVENTOUT_36") (pintype "passive"))
    )
    (net (code "85") (name "unconnected-(U1-PC3{slash}SPI2_MOSI{slash}I2S2_SD{slash}OTG_HS_ULPI_NXT{slash}ETH_MII_TX_CLK{slash}ADC123_IN13-Pad18)") (class "Default")
      (node (ref "U1") (pin "18") (pinfunction "PC3/SPI2_MOSI/I2S2_SD/OTG_HS_ULPI_NXT/ETH_MII_TX_CLK/ADC123_IN13_18") (pintype "passive"))
    )
    (net (code "86") (name "unconnected-(U1-PC4{slash}ETH_RMII_RX_D0{slash}ETH_MII_RX_D0{slash}ADC12_IN14-Pad32)") (class "Default")
      (node (ref "U1") (pin "32") (pinfunction "PC4/ETH_RMII_RX_D0/ETH_MII_RX_D0/ADC12_IN14_32") (pintype "passive"))
    )
    (net (code "87") (name "unconnected-(U1-PC5{slash}ETH_RMII_RX_D1{slash}ETH_MII_RX_D1{slash}ADC12_IN15-Pad33)") (class "Default")
      (node (ref "U1") (pin "33") (pinfunction "PC5/ETH_RMII_RX_D1/ETH_MII_RX_D1/ADC12_IN15_33") (pintype "passive"))
    )
    (net (code "88") (name "unconnected-(U1-PC13{slash}RTC_AF1-Pad7)") (class "Default")
      (node (ref "U1") (pin "7") (pinfunction "PC13/RTC_AF1_7") (pintype "passive"))
    )
    (net (code "89") (name "unconnected-(U1-PC14{slash}OSC32_IN-Pad8)") (class "Default")
      (node (ref "U1") (pin "8") (pinfunction "PC14/OSC32_IN_8") (pintype "passive"))
    )
    (net (code "90") (name "unconnected-(U1-PC15{slash}OSC32_OUT-Pad9)") (class "Default")
      (node (ref "U1") (pin "9") (pinfunction "PC15/OSC32_OUT_9") (pintype "passive"))
    )
    (net (code "91") (name "unconnected-(U1-PD10{slash}FSMC_D15{slash}USART3_CK-Pad57)") (class "Default")
      (node (ref "U1") (pin "57") (pinfunction "PD10/FSMC_D15/USART3_CK_57") (pintype "passive"))
    )
    (net (code "92") (name "unconnected-(U1-PD11{slash}FSMC_A16{slash}USART3_CTS-Pad58)") (class "Default")
      (node (ref "U1") (pin "58") (pinfunction "PD11/FSMC_A16/USART3_CTS_58") (pintype "passive"))
    )
    (net (code "93") (name "unconnected-(U1-PD15{slash}FSMC_D1{slash}TIM4_CH4-Pad62)") (class "Default")
      (node (ref "U1") (pin "62") (pinfunction "PD15/FSMC_D1/TIM4_CH4_62") (pintype "passive"))
    )
    (net (code "94") (name "unconnected-(U1-PE3{slash}TRACED0{slash}FSMC_A19-Pad2)") (class "Default")
      (node (ref "U1") (pin "2") (pinfunction "PE3/TRACED0/FSMC_A19_2") (pintype "passive"))
    )
    (net (code "95") (name "unconnected-(U1-PE7{slash}FSMC_D4{slash}TIM1_ETR-Pad37)") (class "Default")
      (node (ref "U1") (pin "37") (pinfunction "PE7/FSMC_D4/TIM1_ETR_37") (pintype "passive"))
    )
    (net (code "96") (name "unconnected-(U1-PE8{slash}FSMC_D5{slash}TIM1_CH1N-Pad38)") (class "Default")
      (node (ref "U1") (pin "38") (pinfunction "PE8/FSMC_D5/TIM1_CH1N_38") (pintype "passive"))
    )
    (net (code "97") (name "unconnected-(U1-PE9{slash}FSMC_D6{slash}TIM1_CH1-Pad39)") (class "Default")
      (node (ref "U1") (pin "39") (pinfunction "PE9/FSMC_D6/TIM1_CH1_39") (pintype "passive"))
    )
    (net (code "98") (name "unconnected-(U1-PE10{slash}FSMC_D7{slash}TIM1_CH2N-Pad40)") (class "Default")
      (node (ref "U1") (pin "40") (pinfunction "PE10/FSMC_D7/TIM1_CH2N_40") (pintype "passive"))
    )
    (net (code "99") (name "unconnected-(U1-PE11{slash}FSMC_D8{slash}TIM1_CH2-Pad41)") (class "Default")
      (node (ref "U1") (pin "41") (pinfunction "PE11/FSMC_D8/TIM1_CH2_41") (pintype "passive"))
    )
    (net (code "100") (name "unconnected-(U1-PE12{slash}FSMC_D9{slash}TIM1_CH3N-Pad42)") (class "Default")
      (node (ref "U1") (pin "42") (pinfunction "PE12/FSMC_D9/TIM1_CH3N_42") (pintype "passive"))
    )
    (net (code "101") (name "unconnected-(U1-PE13{slash}FSMC_D10{slash}TIM1_CH3-Pad43)") (class "Default")
      (node (ref "U1") (pin "43") (pinfunction "PE13/FSMC_D10/TIM1_CH3_43") (pintype "passive"))
    )
    (net (code "102") (name "unconnected-(U1-PE14{slash}FSMC_D11{slash}TIM1_CH4-Pad44)") (class "Default")
      (node (ref "U1") (pin "44") (pinfunction "PE14/FSMC_D11/TIM1_CH4_44") (pintype "passive"))
    )
    (net (code "103") (name "unconnected-(U1-PE15FSMC_D12{slash}TIM1_BKIN-Pad45)") (class "Default")
      (node (ref "U1") (pin "45") (pinfunction "PE15FSMC_D12/TIM1_BKIN_45") (pintype "passive"))
    )
    (net (code "104") (name "unconnected-(U2-D0-Pad24)") (class "Default")
      (node (ref "U2") (pin "24") (pinfunction "D0_24") (pintype "passive"))
    )
    (net (code "105") (name "unconnected-(U2-D1-Pad23)") (class "Default")
      (node (ref "U2") (pin "23") (pinfunction "D1_23") (pintype "passive"))
    )
    (net (code "106") (name "unconnected-(U2-NC-Pad1)") (class "Default")
      (node (ref "U2") (pin "1") (pinfunction "NC_1") (pintype "passive"))
    )
    (net (code "107") (name "unconnected-(USB1-ID-Pad4)") (class "Default")
      (node (ref "USB1") (pin "4") (pinfunction "ID_4") (pintype "passive"))
    )
  )
)
